# GPIO.net
KiCad netlist of a schematic drawn in Altium Designer
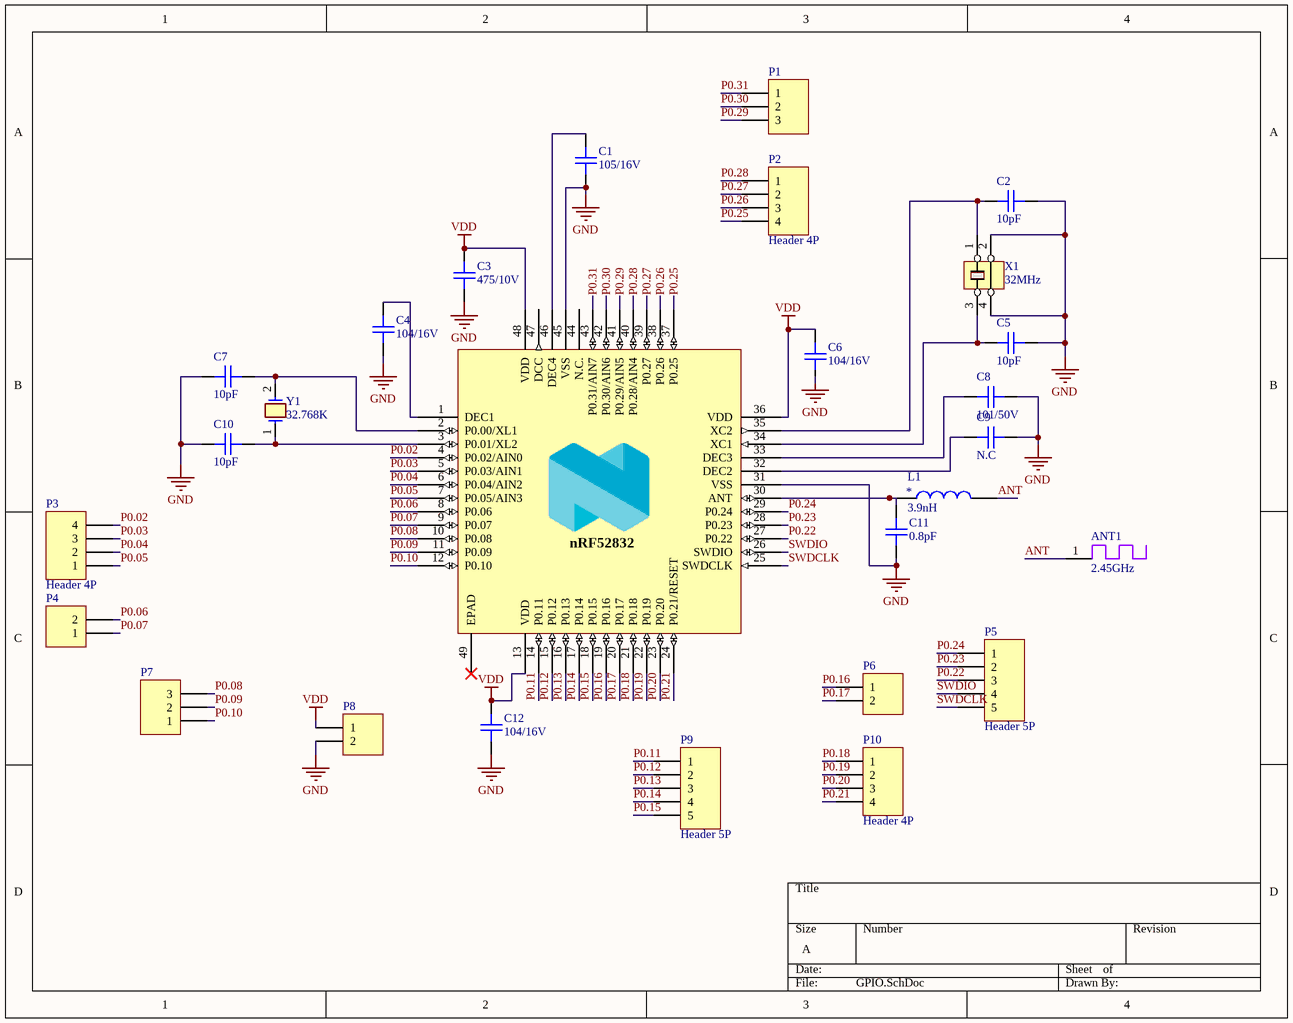
[diagram p0: GPIO.SchDoc]

(export (version "E")
  (design (tool "Eeschema 10.0.6"))
  (components
    (comp (ref "ANT1")
      (value "2.45GHz")
      (footprint "PATCH ANTEN 2.45GHZ")
      (description "PCB ANTENNA 2.45GHZ")
      (libsource (lib "06.PCB Anten") (part "PCB antenna 2.45GHZ"))
    )
    (comp (ref "C1")
      (value "105/16V")
      (footprint "CAPC-0603 (1608)")
      (description "CAP CER 1uF 10% 16V X7R 0603")
      (fields (field (name "MPN") "CC0603KRX7R7BB105"))
      (libsource (lib "01.Passives") (part "CC0603KRX7R7BB105"))
    )
    (comp (ref "C2")
      (value "10pF")
      (footprint "CAPC-0402 (1005)")
      (description "CAP CER 10PF 25V C0G/NP0 0402")
      (fields (field (name "MPN") "C0402C100J3GACTU") (field (name "MFR") "KEMET"))
      (libsource (lib "01.Passives") (part "C0402C100J3GACTU"))
    )
    (comp (ref "C3")
      (value "475/10V")
      (footprint "CAPC-0603 (1608)")
      (description "CAP CER 4.7uF 10% 10V X5R 0603")
      (fields (field (name "MPN") "CL10A475KP8NNNC"))
      (libsource (lib "01.Passives") (part "CL10A475KP8NNNC"))
    )
    (comp (ref "C4")
      (value "104/16V")
      (footprint "CAPC-0402 (1005)")
      (description "CAP CER 0.1UF 16V X7R 0402")
      (fields (field (name "MPN") "CC0402KRX7R7BB104") (field (name "MFR") "Yageo"))
      (libsource (lib "01.Passives") (part "CC0402KRX7R7BB104"))
    )
    (comp (ref "C5")
      (value "10pF")
      (footprint "CAPC-0402 (1005)")
      (description "CAP CER 10PF 25V C0G/NP0 0402")
      (fields (field (name "MPN") "C0402C100J3GACTU") (field (name "MFR") "KEMET"))
      (libsource (lib "01.Passives") (part "C0402C100J3GACTU"))
    )
    (comp (ref "C6")
      (value "104/16V")
      (footprint "CAPC-0402 (1005)")
      (description "CAP CER 0.1UF 16V X7R 0402")
      (fields (field (name "MPN") "CC0402KRX7R7BB104") (field (name "MFR") "Yageo"))
      (libsource (lib "01.Passives") (part "CC0402KRX7R7BB104"))
    )
    (comp (ref "C7")
      (value "10pF")
      (footprint "CAPC-0402 (1005)")
      (description "CAP CER 10PF 25V C0G/NP0 0402")
      (fields (field (name "MPN") "C0402C100J3GACTU") (field (name "MFR") "KEMET"))
      (libsource (lib "01.Passives") (part "C0402C100J3GACTU"))
    )
    (comp (ref "C8")
      (value "101/50V")
      (footprint "CAPC-0603 (1608)")
      (description "CAP CER 100pF 5% 50V C0G/NP0 0603")
      (fields (field (name "MPN") "GRM1885C1H101JA01D"))
      (libsource (lib "01.Passives") (part "GRM1885C1H101JA01D"))
    )
    (comp (ref "C9")
      (value "N.C")
      (footprint "CAPC-0603 (1608)")
      (description "CAP CER 100pF 5% 50V C0G/NP0 0603")
      (fields (field (name "MPN") "GRM1885C1H101JA01D"))
      (libsource (lib "01.Passives") (part "GRM1885C1H101JA01D"))
    )
    (comp (ref "C10")
      (value "10pF")
      (footprint "CAPC-0402 (1005)")
      (description "CAP CER 10PF 25V C0G/NP0 0402")
      (fields (field (name "MPN") "C0402C100J3GACTU") (field (name "MFR") "KEMET"))
      (libsource (lib "01.Passives") (part "C0402C100J3GACTU"))
    )
    (comp (ref "C11")
      (value "0.8pF")
      (footprint "CAPC-0402 (1005)")
      (description "CAP CER 10PF 25V C0G/NP0 0402")
      (fields (field (name "MPN") "C0402C100J3GACTU") (field (name "MFR") "KEMET"))
      (libsource (lib "01.Passives") (part "C0402C100J3GACTU"))
    )
    (comp (ref "C12")
      (value "104/16V")
      (footprint "CAPC-0402 (1005)")
      (description "CAP CER 0.1UF 16V X7R 0402")
      (fields (field (name "MPN") "CC0402KRX7R7BB104") (field (name "MFR") "Yageo"))
      (libsource (lib "01.Passives") (part "CC0402KRX7R7BB104"))
    )
    (comp (ref "L1")
      (value "3.9nH")
      (footprint "IND-0603 (1608)")
      (description "FIXED IND 3.9NH 300MA 140 MOHM")
      (fields (field (name "MPN") "HK16083N9S-T"))
      (libsource (lib "01.Passives") (part "HK16083N9S-T"))
    )
    (comp (ref "P1")
      (value "~")
      (footprint "HDR1X3")
      (description "Header, 3-Pin, pitch 2.54mm")
      (libsource (lib "") (part "Header 3x1_1"))
    )
    (comp (ref "P2")
      (value "Header 4P")
      (footprint "HDR1X4")
      (description "Header, 4 Pin Pitch 2.54mm")
      (fields (field (name "MPN") "S1012EC-40-ND"))
      (libsource (lib "") (part "Header 4x1_1"))
    )
    (comp (ref "P3")
      (value "Header 4P")
      (footprint "HDR1X4")
      (description "Header, 4 Pin Pitch 2.54mm")
      (fields (field (name "MPN") "S1012EC-40-ND"))
      (libsource (lib "04.Header-Connecter") (part "Header 4x1"))
    )
    (comp (ref "P4")
      (value "~")
      (footprint "HDR1X2")
      (description "Header, 2-Pin, pitch 2.54mm")
      (libsource (lib "04.Header-Connecter") (part "Header 2x1"))
    )
    (comp (ref "P5")
      (value "Header 5P")
      (footprint "HDR1X5")
      (description "Header, 5 Pin Pitch 2.54mm")
      (fields (field (name "MPN") "S1012EC-40-ND"))
      (libsource (lib "04.Header-Connecter") (part "Header 5x1"))
    )
    (comp (ref "P6")
      (value "~")
      (footprint "HDR1X2")
      (description "Header, 2-Pin, pitch 2.54mm")
      (libsource (lib "") (part "Header 2x1_1"))
    )
    (comp (ref "P7")
      (value "~")
      (footprint "HDR1X3")
      (description "Header, 3-Pin, pitch 2.54mm")
      (libsource (lib "04.Header-Connecter") (part "Header 3x1"))
    )
    (comp (ref "P8")
      (value "~")
      (footprint "HDR1X2")
      (description "Header, 2-Pin, pitch 2.54mm")
      (libsource (lib "") (part "Header 2x1_1"))
    )
    (comp (ref "P9")
      (value "Header 5P")
      (footprint "HDR1X5")
      (description "Header, 5 Pin Pitch 2.54mm")
      (fields (field (name "MPN") "S1012EC-40-ND"))
      (libsource (lib "04.Header-Connecter") (part "Header 5x1"))
    )
    (comp (ref "P10")
      (value "Header 4P")
      (footprint "HDR1X4")
      (description "Header, 4 Pin Pitch 2.54mm")
      (fields (field (name "MPN") "S1012EC-40-ND"))
      (libsource (lib "") (part "Header 4x1_1"))
    )
    (comp (ref "U1")
      (value "nRF52832_QFAA")
      (footprint "48-VFQFN")
      (description "Multi-protocol Bluetooth low energy, ANT, and 2.4 GHz proprietary system on chip")
      (fields (field (name "MFR") "Nordic Semiconductor"))
      (libsource (lib "05.IC") (part "nRF52832_QFAA"))
    )
    (comp (ref "X1")
      (value "32MHz")
      (footprint "CRYSTAL-XRCGB27M120F3M10R0 (2x1.6)")
      (description "XTAL 32MHZ 8PF SMD")
      (fields (field (name "MPN") "R2016-32.000-8-F-1010-EXT-TR") (field (name "MFR") "Raltron Electronics"))
      (libsource (lib "01.Passives") (part "R2016-32.000-8-F-1010-EXT-TR"))
    )
    (comp (ref "Y1")
      (value "32.768K")
      (footprint "NX3215SA-32.768K-STD-MUA-14:XTAL_NX3215SA-32.768K-STD-MUA-14")
      (description "32.768kHz Â±20ppm Crystal 6pF 70 kOhms 2-SMD, No Lead  MANUFACTURER: NIHON DEMPA KOGYO")
      (fields
        (field (name "MF") "{'manufacturer': u'NDK America,'}")
        (field (name "MP") "NX3215SA-32.768K-STD-MUA-14")
      )
      (libsource (lib "NX3215SA-32.768K-STD-MUA-14") (part "NX3215SA-32.768K-STD-MUA-14"))
    )
  )
  (nets
    (net (code "1") (name "/ANT") (class "Default")
      (node (ref "ANT1") (pin "1") (pinfunction "ANT_1") (pintype "passive"))
      (node (ref "L1") (pin "2") (pinfunction "2_2") (pintype "passive"))
    )
    (net (code "2") (name "/P0.02") (class "Default")
      (node (ref "P3") (pin "4") (pinfunction "4_4") (pintype "passive"))
      (node (ref "U1") (pin "4") (pinfunction "P0.02/AIN0_4") (pintype "bidirectional"))
    )
    (net (code "3") (name "/P0.03") (class "Default")
      (node (ref "P3") (pin "3") (pinfunction "3_3") (pintype "passive"))
      (node (ref "U1") (pin "5") (pinfunction "P0.03/AIN1_5") (pintype "bidirectional"))
    )
    (net (code "4") (name "/P0.04") (class "Default")
      (node (ref "P3") (pin "2") (pinfunction "2_2") (pintype "passive"))
      (node (ref "U1") (pin "6") (pinfunction "P0.04/AIN2_6") (pintype "bidirectional"))
    )
    (net (code "5") (name "/P0.05") (class "Default")
      (node (ref "P3") (pin "1") (pinfunction "1_1") (pintype "passive"))
      (node (ref "U1") (pin "7") (pinfunction "P0.05/AIN3_7") (pintype "bidirectional"))
    )
    (net (code "6") (name "/P0.06") (class "Default")
      (node (ref "P4") (pin "2") (pinfunction "2_2") (pintype "passive"))
      (node (ref "U1") (pin "8") (pinfunction "P0.06_8") (pintype "bidirectional"))
    )
    (net (code "7") (name "/P0.07") (class "Default")
      (node (ref "P4") (pin "1") (pinfunction "1_1") (pintype "passive"))
      (node (ref "U1") (pin "9") (pinfunction "P0.07_9") (pintype "bidirectional"))
    )
    (net (code "8") (name "/P0.08") (class "Default")
      (node (ref "P7") (pin "3") (pinfunction "3_3") (pintype "passive"))
      (node (ref "U1") (pin "10") (pinfunction "P0.08_10") (pintype "bidirectional"))
    )
    (net (code "9") (name "/P0.09") (class "Default")
      (node (ref "P7") (pin "2") (pinfunction "2_2") (pintype "passive"))
      (node (ref "U1") (pin "11") (pinfunction "P0.09_11") (pintype "bidirectional"))
    )
    (net (code "10") (name "/P0.10") (class "Default")
      (node (ref "P7") (pin "1") (pinfunction "1_1") (pintype "passive"))
      (node (ref "U1") (pin "12") (pinfunction "P0.10_12") (pintype "bidirectional"))
    )
    (net (code "11") (name "/P0.11") (class "Default")
      (node (ref "P9") (pin "1") (pinfunction "1_1") (pintype "passive"))
      (node (ref "U1") (pin "14") (pinfunction "P0.11_14") (pintype "bidirectional"))
    )
    (net (code "12") (name "/P0.12") (class "Default")
      (node (ref "P9") (pin "2") (pinfunction "2_2") (pintype "passive"))
      (node (ref "U1") (pin "15") (pinfunction "P0.12_15") (pintype "bidirectional"))
    )
    (net (code "13") (name "/P0.13") (class "Default")
      (node (ref "P9") (pin "3") (pinfunction "3_3") (pintype "passive"))
      (node (ref "U1") (pin "16") (pinfunction "P0.13_16") (pintype "bidirectional"))
    )
    (net (code "14") (name "/P0.14") (class "Default")
      (node (ref "P9") (pin "4") (pinfunction "4_4") (pintype "passive"))
      (node (ref "U1") (pin "17") (pinfunction "P0.14_17") (pintype "bidirectional"))
    )
    (net (code "15") (name "/P0.15") (class "Default")
      (node (ref "P9") (pin "5") (pinfunction "5_5") (pintype "passive"))
      (node (ref "U1") (pin "18") (pinfunction "P0.15_18") (pintype "bidirectional"))
    )
    (net (code "16") (name "/P0.16") (class "Default")
      (node (ref "P6") (pin "1") (pinfunction "1_1") (pintype "passive"))
      (node (ref "U1") (pin "19") (pinfunction "P0.16_19") (pintype "bidirectional"))
    )
    (net (code "17") (name "/P0.17") (class "Default")
      (node (ref "P6") (pin "2") (pinfunction "2_2") (pintype "passive"))
      (node (ref "U1") (pin "20") (pinfunction "P0.17_20") (pintype "bidirectional"))
    )
    (net (code "18") (name "/P0.18") (class "Default")
      (node (ref "P10") (pin "1") (pinfunction "1_1") (pintype "passive"))
      (node (ref "U1") (pin "21") (pinfunction "P0.18_21") (pintype "bidirectional"))
    )
    (net (code "19") (name "/P0.19") (class "Default")
      (node (ref "P10") (pin "2") (pinfunction "2_2") (pintype "passive"))
      (node (ref "U1") (pin "22") (pinfunction "P0.19_22") (pintype "bidirectional"))
    )
    (net (code "20") (name "/P0.20") (class "Default")
      (node (ref "P10") (pin "3") (pinfunction "3_3") (pintype "passive"))
      (node (ref "U1") (pin "23") (pinfunction "P0.20_23") (pintype "bidirectional"))
    )
    (net (code "21") (name "/P0.21") (class "Default")
      (node (ref "P10") (pin "4") (pinfunction "4_4") (pintype "passive"))
      (node (ref "U1") (pin "24") (pinfunction "P0.21/RESET_24") (pintype "bidirectional"))
    )
    (net (code "22") (name "/P0.22") (class "Default")
      (node (ref "P5") (pin "3") (pinfunction "3_3") (pintype "passive"))
      (node (ref "U1") (pin "27") (pinfunction "P0.22_27") (pintype "bidirectional"))
    )
    (net (code "23") (name "/P0.23") (class "Default")
      (node (ref "P5") (pin "2") (pinfunction "2_2") (pintype "passive"))
      (node (ref "U1") (pin "28") (pinfunction "P0.23_28") (pintype "bidirectional"))
    )
    (net (code "24") (name "/P0.24") (class "Default")
      (node (ref "P5") (pin "1") (pinfunction "1_1") (pintype "passive"))
      (node (ref "U1") (pin "29") (pinfunction "P0.24_29") (pintype "bidirectional"))
    )
    (net (code "25") (name "/P0.25") (class "Default")
      (node (ref "P2") (pin "4") (pinfunction "4_4") (pintype "passive"))
      (node (ref "U1") (pin "37") (pinfunction "P0.25_37") (pintype "bidirectional"))
    )
    (net (code "26") (name "/P0.26") (class "Default")
      (node (ref "P2") (pin "3") (pinfunction "3_3") (pintype "passive"))
      (node (ref "U1") (pin "38") (pinfunction "P0.26_38") (pintype "bidirectional"))
    )
    (net (code "27") (name "/P0.27") (class "Default")
      (node (ref "P2") (pin "2") (pinfunction "2_2") (pintype "passive"))
      (node (ref "U1") (pin "39") (pinfunction "P0.27_39") (pintype "bidirectional"))
    )
    (net (code "28") (name "/P0.28") (class "Default")
      (node (ref "P2") (pin "1") (pinfunction "1_1") (pintype "passive"))
      (node (ref "U1") (pin "40") (pinfunction "P0.28/AIN4_40") (pintype "bidirectional"))
    )
    (net (code "29") (name "/P0.29") (class "Default")
      (node (ref "P1") (pin "3") (pinfunction "3_3") (pintype "passive"))
      (node (ref "U1") (pin "41") (pinfunction "P0.29/AIN5_41") (pintype "bidirectional"))
    )
    (net (code "30") (name "/P0.30") (class "Default")
      (node (ref "P1") (pin "2") (pinfunction "2_2") (pintype "passive"))
      (node (ref "U1") (pin "42") (pinfunction "P0.30/AIN6_42") (pintype "bidirectional"))
    )
    (net (code "31") (name "/P0.31") (class "Default")
      (node (ref "P1") (pin "1") (pinfunction "1_1") (pintype "passive"))
      (node (ref "U1") (pin "43") (pinfunction "P0.31/AIN7_43") (pintype "bidirectional"))
    )
    (net (code "32") (name "/SWDCLK") (class "Default")
      (node (ref "P5") (pin "5") (pinfunction "5_5") (pintype "passive"))
      (node (ref "U1") (pin "25") (pinfunction "SWDCLK_25") (pintype "input"))
    )
    (net (code "33") (name "/SWDIO") (class "Default")
      (node (ref "P5") (pin "4") (pinfunction "4_4") (pintype "passive"))
      (node (ref "U1") (pin "26") (pinfunction "SWDIO_26") (pintype "bidirectional"))
    )
    (net (code "34") (name "GND") (class "Default")
      (node (ref "C1") (pin "2") (pinfunction "2_2") (pintype "passive"))
      (node (ref "C10") (pin "1") (pinfunction "1_1") (pintype "passive"))
      (node (ref "C11") (pin "1") (pinfunction "1_1") (pintype "passive"))
      (node (ref "C12") (pin "1") (pinfunction "1_1") (pintype "passive"))
      (node (ref "C2") (pin "1") (pinfunction "1_1") (pintype "passive"))
      (node (ref "C3") (pin "1") (pinfunction "1_1") (pintype "passive"))
      (node (ref "C4") (pin "1") (pinfunction "1_1") (pintype "passive"))
      (node (ref "C5") (pin "1") (pinfunction "1_1") (pintype "passive"))
      (node (ref "C6") (pin "1") (pinfunction "1_1") (pintype "passive"))
      (node (ref "C7") (pin "1") (pinfunction "1_1") (pintype "passive"))
      (node (ref "C8") (pin "1") (pinfunction "1_1") (pintype "passive"))
      (node (ref "C9") (pin "1") (pinfunction "1_1") (pintype "passive"))
      (node (ref "P8") (pin "2") (pinfunction "2_2") (pintype "passive"))
      (node (ref "U1") (pin "31") (pinfunction "VSS_31") (pintype "power_in"))
      (node (ref "U1") (pin "45") (pinfunction "VSS_45") (pintype "power_in"))
      (node (ref "X1") (pin "2") (pinfunction "2_2") (pintype "passive"))
      (node (ref "X1") (pin "4") (pinfunction "4_4") (pintype "passive"))
    )
    (net (code "35") (name "Net-(U1-ANT)") (class "Default")
      (node (ref "C11") (pin "2") (pinfunction "2_2") (pintype "passive"))
      (node (ref "L1") (pin "1") (pinfunction "1_1") (pintype "passive"))
      (node (ref "U1") (pin "30") (pinfunction "ANT_30") (pintype "bidirectional"))
    )
    (net (code "36") (name "Net-(U1-DEC1)") (class "Default")
      (node (ref "C4") (pin "2") (pinfunction "2_2") (pintype "passive"))
      (node (ref "U1") (pin "1") (pinfunction "DEC1_1") (pintype "power_in"))
    )
    (net (code "37") (name "Net-(U1-DEC2)") (class "Default")
      (node (ref "C9") (pin "2") (pinfunction "2_2") (pintype "passive"))
      (node (ref "U1") (pin "32") (pinfunction "DEC2_32") (pintype "power_in"))
    )
    (net (code "38") (name "Net-(U1-DEC3)") (class "Default")
      (node (ref "C8") (pin "2") (pinfunction "2_2") (pintype "passive"))
      (node (ref "U1") (pin "33") (pinfunction "DEC3_33") (pintype "power_in"))
    )
    (net (code "39") (name "Net-(U1-DEC4)") (class "Default")
      (node (ref "C1") (pin "1") (pinfunction "1_1") (pintype "passive"))
      (node (ref "U1") (pin "46") (pinfunction "DEC4_46") (pintype "power_in"))
    )
    (net (code "40") (name "Net-(U1-P0.00{slash}XL1)") (class "Default")
      (node (ref "C7") (pin "2") (pinfunction "2_2") (pintype "passive"))
      (node (ref "U1") (pin "2") (pinfunction "P0.00/XL1_2") (pintype "bidirectional"))
      (node (ref "Y1") (pin "2") (pinfunction "2_2") (pintype "passive"))
    )
    (net (code "41") (name "Net-(U1-P0.01{slash}XL2)") (class "Default")
      (node (ref "C10") (pin "2") (pinfunction "2_2") (pintype "passive"))
      (node (ref "U1") (pin "3") (pinfunction "P0.01/XL2_3") (pintype "bidirectional"))
      (node (ref "Y1") (pin "1") (pinfunction "1_1") (pintype "passive"))
    )
    (net (code "42") (name "Net-(U1-XC1)") (class "Default")
      (node (ref "C5") (pin "2") (pinfunction "2_2") (pintype "passive"))
      (node (ref "U1") (pin "34") (pinfunction "XC1_34") (pintype "input"))
      (node (ref "X1") (pin "3") (pinfunction "3_3") (pintype "passive"))
    )
    (net (code "43") (name "Net-(U1-XC2)") (class "Default")
      (node (ref "C2") (pin "2") (pinfunction "2_2") (pintype "passive"))
      (node (ref "U1") (pin "35") (pinfunction "XC2_35") (pintype "output"))
      (node (ref "X1") (pin "1") (pinfunction "1_1") (pintype "passive"))
    )
    (net (code "44") (name "VDD") (class "Default")
      (node (ref "C12") (pin "2") (pinfunction "2_2") (pintype "passive"))
      (node (ref "C3") (pin "2") (pinfunction "2_2") (pintype "passive"))
      (node (ref "C6") (pin "2") (pinfunction "2_2") (pintype "passive"))
      (node (ref "P8") (pin "1") (pinfunction "1_1") (pintype "passive"))
      (node (ref "U1") (pin "13") (pinfunction "VDD_13") (pintype "power_in"))
      (node (ref "U1") (pin "36") (pinfunction "VDD_36") (pintype "power_in"))
      (node (ref "U1") (pin "48") (pinfunction "VDD_48") (pintype "power_in"))
    )
    (net (code "45") (name "unconnected-(U1-DCC-Pad47)") (class "Default")
      (node (ref "U1") (pin "47") (pinfunction "DCC_47") (pintype "output"))
    )
    (net (code "46") (name "unconnected-(U1-EPAD-Pad49)") (class "Default")
      (node (ref "U1") (pin "49") (pinfunction "EPAD_49") (pintype "power_in+no_connect"))
    )
    (net (code "47") (name "unconnected-(U1-N.C.-Pad44)") (class "Default")
      (node (ref "U1") (pin "44") (pinfunction "N.C._44") (pintype "power_in"))
    )
  )
)
